# SPI_Bus_Buffer.net
KiCad netlist of a schematic drawn in EAGLE
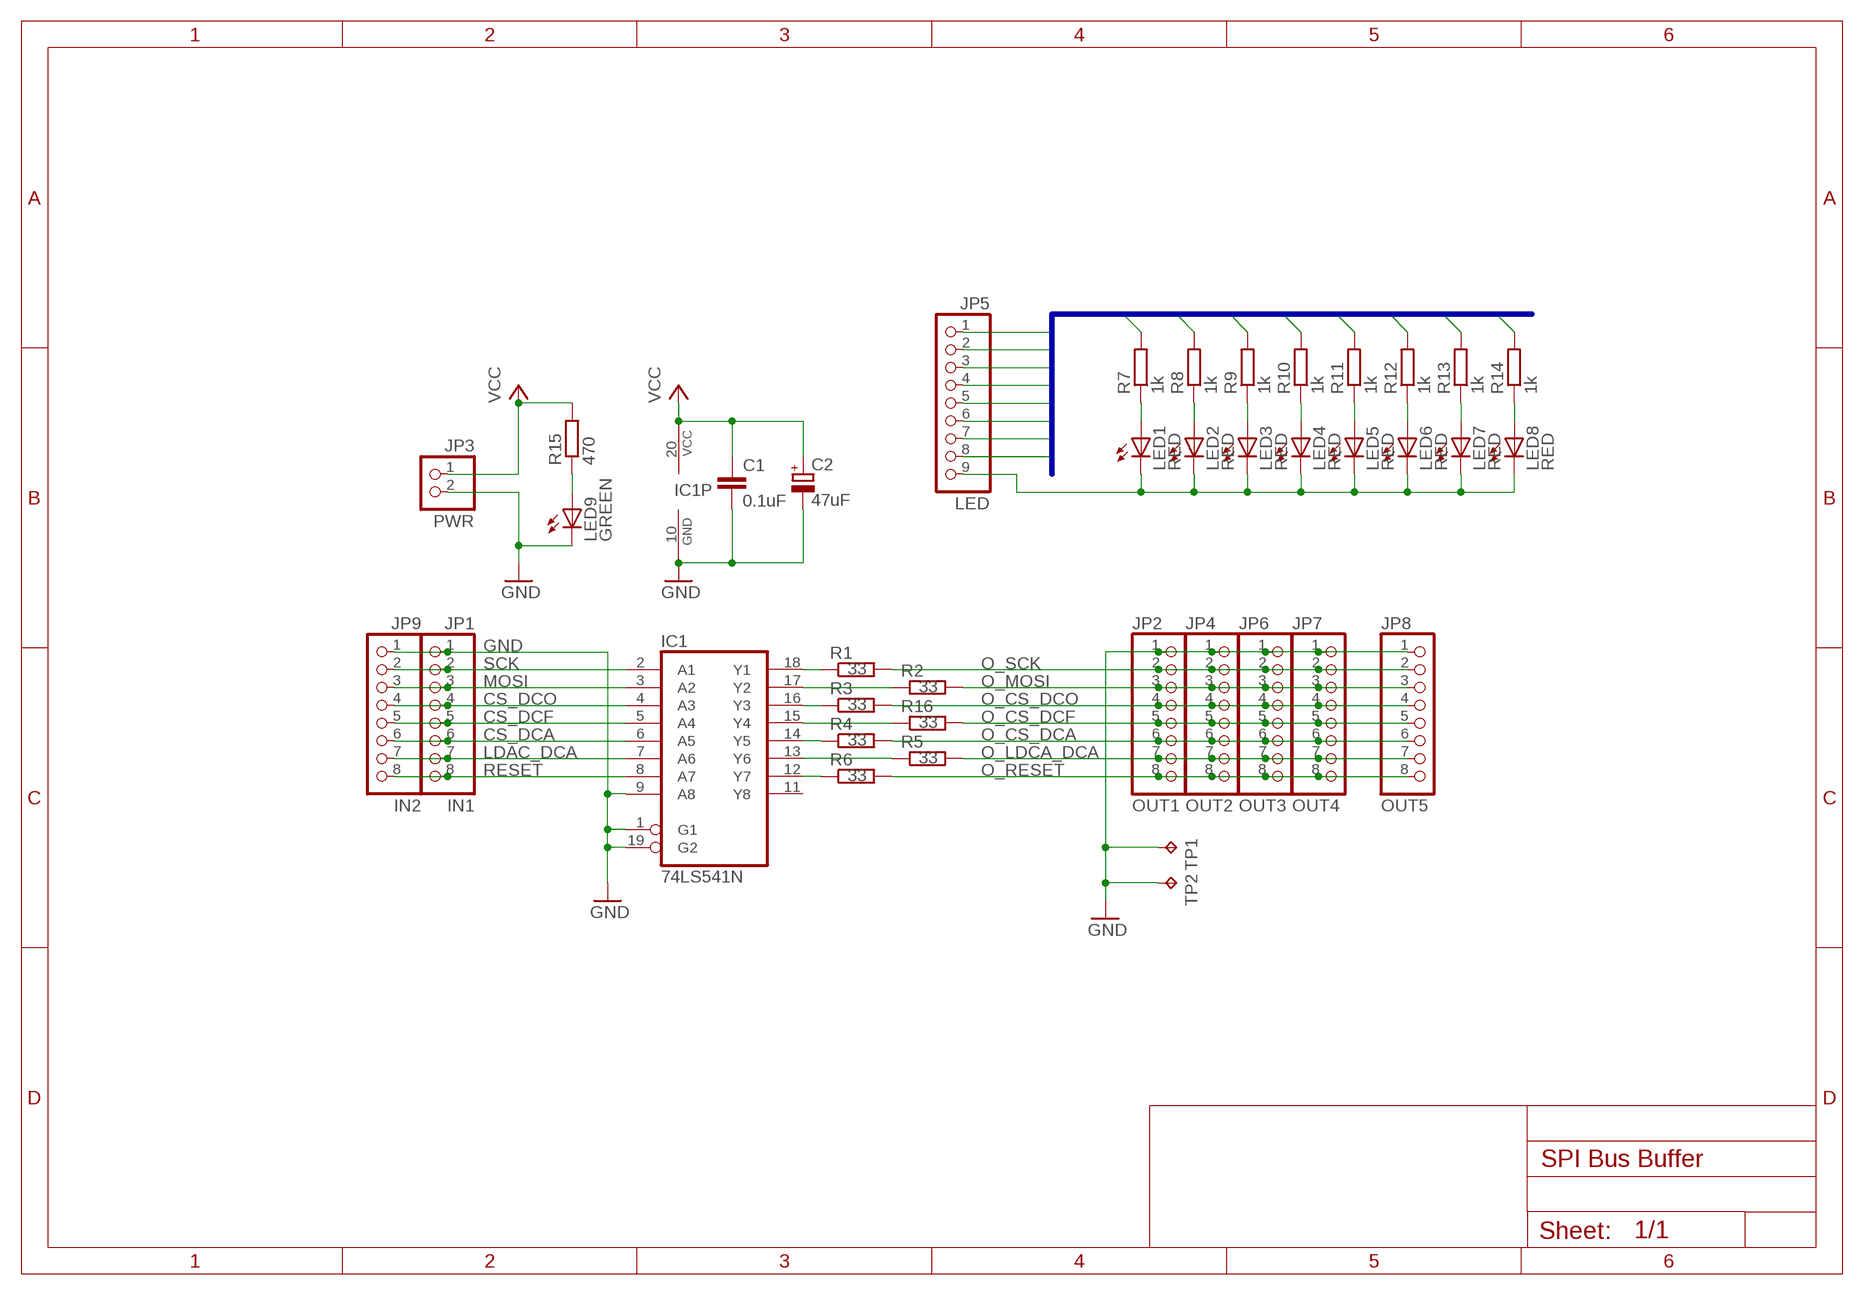
[diagram p0: schematic, sheet 1]

(export (version "E")
  (design (tool "Eeschema 10.0.6"))
  (components
    (comp (ref "C1")
      (value "0.1uF")
      (footprint "eagle-import:C050-024X044")
      (libsource (lib "eagle-import") (part "C-EU050-024X044"))
    )
    (comp (ref "C2")
      (value "47uF")
      (footprint "eagle-import:E2,5-5")
      (libsource (lib "eagle-import") (part "CPOL-EUE2.5-5"))
    )
    (comp (ref "IC1")
      (value "74LS541N")
      (footprint "eagle-import:DIL20")
      (libsource (lib "eagle-import") (part "74541NLS"))
    )
    (comp (ref "JP1")
      (value "IN1")
      (footprint "eagle-import:1X08")
      (libsource (lib "eagle-import") (part "PINHD-1X8"))
    )
    (comp (ref "JP2")
      (value "OUT1")
      (footprint "eagle-import:1X08")
      (libsource (lib "eagle-import") (part "PINHD-1X8"))
    )
    (comp (ref "JP3")
      (value "PWR")
      (footprint "eagle-import:1X02")
      (libsource (lib "eagle-import") (part "PINHD-1X2"))
    )
    (comp (ref "JP4")
      (value "OUT2")
      (footprint "eagle-import:1X08")
      (libsource (lib "eagle-import") (part "PINHD-1X8"))
    )
    (comp (ref "JP5")
      (value "LED")
      (footprint "eagle-import:1X09")
      (libsource (lib "eagle-import") (part "PINHD-1X9"))
    )
    (comp (ref "JP6")
      (value "OUT3")
      (footprint "eagle-import:1X08")
      (libsource (lib "eagle-import") (part "PINHD-1X8"))
    )
    (comp (ref "JP7")
      (value "OUT4")
      (footprint "eagle-import:1X08")
      (libsource (lib "eagle-import") (part "PINHD-1X8"))
    )
    (comp (ref "JP8")
      (value "OUT5")
      (footprint "eagle-import:1X08")
      (libsource (lib "eagle-import") (part "PINHD-1X8"))
    )
    (comp (ref "JP9")
      (value "IN2")
      (footprint "eagle-import:1X08")
      (libsource (lib "eagle-import") (part "PINHD-1X8"))
    )
    (comp (ref "LED1")
      (value "RED")
      (footprint "eagle-import:LED3MM")
      (libsource (lib "eagle-import") (part "LED3MM"))
    )
    (comp (ref "LED2")
      (value "RED")
      (footprint "eagle-import:LED3MM")
      (libsource (lib "eagle-import") (part "LED3MM"))
    )
    (comp (ref "LED3")
      (value "RED")
      (footprint "eagle-import:LED3MM")
      (libsource (lib "eagle-import") (part "LED3MM"))
    )
    (comp (ref "LED4")
      (value "RED")
      (footprint "eagle-import:LED3MM")
      (libsource (lib "eagle-import") (part "LED3MM"))
    )
    (comp (ref "LED5")
      (value "RED")
      (footprint "eagle-import:LED3MM")
      (libsource (lib "eagle-import") (part "LED3MM"))
    )
    (comp (ref "LED6")
      (value "RED")
      (footprint "eagle-import:LED3MM")
      (libsource (lib "eagle-import") (part "LED3MM"))
    )
    (comp (ref "LED7")
      (value "RED")
      (footprint "eagle-import:LED3MM")
      (libsource (lib "eagle-import") (part "LED3MM"))
    )
    (comp (ref "LED8")
      (value "RED")
      (footprint "eagle-import:LED3MM")
      (libsource (lib "eagle-import") (part "LED3MM"))
    )
    (comp (ref "LED9")
      (value "GREEN")
      (footprint "eagle-import:LED3MM")
      (libsource (lib "eagle-import") (part "LED3MM"))
    )
    (comp (ref "R1")
      (value "33")
      (footprint "eagle-import:0207_7")
      (libsource (lib "eagle-import") (part "R-EU_0207/7"))
    )
    (comp (ref "R2")
      (value "33")
      (footprint "eagle-import:0207_7")
      (libsource (lib "eagle-import") (part "R-EU_0207/7"))
    )
    (comp (ref "R3")
      (value "33")
      (footprint "eagle-import:0207_7")
      (libsource (lib "eagle-import") (part "R-EU_0207/7"))
    )
    (comp (ref "R4")
      (value "33")
      (footprint "eagle-import:0207_7")
      (libsource (lib "eagle-import") (part "R-EU_0207/7"))
    )
    (comp (ref "R5")
      (value "33")
      (footprint "eagle-import:0207_7")
      (libsource (lib "eagle-import") (part "R-EU_0207/7"))
    )
    (comp (ref "R6")
      (value "33")
      (footprint "eagle-import:0207_7")
      (libsource (lib "eagle-import") (part "R-EU_0207/7"))
    )
    (comp (ref "R7")
      (value "1k")
      (footprint "eagle-import:0207_7")
      (libsource (lib "eagle-import") (part "R-EU_0207/7"))
    )
    (comp (ref "R8")
      (value "1k")
      (footprint "eagle-import:0207_7")
      (libsource (lib "eagle-import") (part "R-EU_0207/7"))
    )
    (comp (ref "R9")
      (value "1k")
      (footprint "eagle-import:0207_7")
      (libsource (lib "eagle-import") (part "R-EU_0207/7"))
    )
    (comp (ref "R10")
      (value "1k")
      (footprint "eagle-import:0207_7")
      (libsource (lib "eagle-import") (part "R-EU_0207/7"))
    )
    (comp (ref "R11")
      (value "1k")
      (footprint "eagle-import:0207_7")
      (libsource (lib "eagle-import") (part "R-EU_0207/7"))
    )
    (comp (ref "R12")
      (value "1k")
      (footprint "eagle-import:0207_7")
      (libsource (lib "eagle-import") (part "R-EU_0207/7"))
    )
    (comp (ref "R13")
      (value "1k")
      (footprint "eagle-import:0207_7")
      (libsource (lib "eagle-import") (part "R-EU_0207/7"))
    )
    (comp (ref "R14")
      (value "1k")
      (footprint "eagle-import:0207_7")
      (libsource (lib "eagle-import") (part "R-EU_0207/7"))
    )
    (comp (ref "R15")
      (value "470")
      (footprint "eagle-import:0207_7")
      (libsource (lib "eagle-import") (part "R-EU_0207/7"))
    )
    (comp (ref "R16")
      (value "33")
      (footprint "eagle-import:0207_7")
      (libsource (lib "eagle-import") (part "R-EU_0207/7"))
    )
    (comp (ref "TP1")
      (value "TPPAD1-13")
      (footprint "eagle-import:P1-13")
      (libsource (lib "eagle-import") (part "TPPAD1-13"))
    )
    (comp (ref "TP2")
      (value "TPPAD1-13")
      (footprint "eagle-import:P1-13")
      (libsource (lib "eagle-import") (part "TPPAD1-13"))
    )
  )
  (nets
    (net (code "1") (name "/CS_DCA") (class "Default")
      (node (ref "IC1") (pin "6") (pinfunction "A5_6") (pintype "input"))
      (node (ref "JP1") (pin "6") (pinfunction "6_6") (pintype "passive"))
      (node (ref "JP9") (pin "6") (pinfunction "6_6") (pintype "passive"))
    )
    (net (code "2") (name "/CS_DCF") (class "Default")
      (node (ref "IC1") (pin "5") (pinfunction "A4_5") (pintype "input"))
      (node (ref "JP1") (pin "5") (pinfunction "5_5") (pintype "passive"))
      (node (ref "JP9") (pin "5") (pinfunction "5_5") (pintype "passive"))
    )
    (net (code "3") (name "/CS_DCO") (class "Default")
      (node (ref "IC1") (pin "4") (pinfunction "A3_4") (pintype "input"))
      (node (ref "JP1") (pin "4") (pinfunction "4_4") (pintype "passive"))
      (node (ref "JP9") (pin "4") (pinfunction "4_4") (pintype "passive"))
    )
    (net (code "4") (name "/LDAC_DCA") (class "Default")
      (node (ref "IC1") (pin "7") (pinfunction "A6_7") (pintype "input"))
      (node (ref "JP1") (pin "7") (pinfunction "7_7") (pintype "passive"))
      (node (ref "JP9") (pin "7") (pinfunction "7_7") (pintype "passive"))
    )
    (net (code "5") (name "/LEDS1") (class "Default")
      (node (ref "JP5") (pin "1") (pinfunction "1_1") (pintype "passive"))
      (node (ref "R7") (pin "2") (pinfunction "2_2") (pintype "passive"))
    )
    (net (code "6") (name "/LEDS2") (class "Default")
      (node (ref "JP5") (pin "2") (pinfunction "2_2") (pintype "passive"))
      (node (ref "R8") (pin "2") (pinfunction "2_2") (pintype "passive"))
    )
    (net (code "7") (name "/LEDS3") (class "Default")
      (node (ref "JP5") (pin "3") (pinfunction "3_3") (pintype "passive"))
      (node (ref "R9") (pin "2") (pinfunction "2_2") (pintype "passive"))
    )
    (net (code "8") (name "/LEDS4") (class "Default")
      (node (ref "JP5") (pin "4") (pinfunction "4_4") (pintype "passive"))
      (node (ref "R10") (pin "2") (pinfunction "2_2") (pintype "passive"))
    )
    (net (code "9") (name "/LEDS5") (class "Default")
      (node (ref "JP5") (pin "5") (pinfunction "5_5") (pintype "passive"))
      (node (ref "R11") (pin "2") (pinfunction "2_2") (pintype "passive"))
    )
    (net (code "10") (name "/LEDS6") (class "Default")
      (node (ref "JP5") (pin "6") (pinfunction "6_6") (pintype "passive"))
      (node (ref "R12") (pin "2") (pinfunction "2_2") (pintype "passive"))
    )
    (net (code "11") (name "/LEDS7") (class "Default")
      (node (ref "JP5") (pin "7") (pinfunction "7_7") (pintype "passive"))
      (node (ref "R13") (pin "2") (pinfunction "2_2") (pintype "passive"))
    )
    (net (code "12") (name "/LEDS8") (class "Default")
      (node (ref "JP5") (pin "8") (pinfunction "8_8") (pintype "passive"))
      (node (ref "R14") (pin "2") (pinfunction "2_2") (pintype "passive"))
    )
    (net (code "13") (name "/MOSI") (class "Default")
      (node (ref "IC1") (pin "3") (pinfunction "A2_3") (pintype "input"))
      (node (ref "JP1") (pin "3") (pinfunction "3_3") (pintype "passive"))
      (node (ref "JP9") (pin "3") (pinfunction "3_3") (pintype "passive"))
    )
    (net (code "14") (name "/O_CS_DCA") (class "Default")
      (node (ref "JP2") (pin "6") (pinfunction "6_6") (pintype "passive"))
      (node (ref "JP4") (pin "6") (pinfunction "6_6") (pintype "passive"))
      (node (ref "JP6") (pin "6") (pinfunction "6_6") (pintype "passive"))
      (node (ref "JP7") (pin "6") (pinfunction "6_6") (pintype "passive"))
      (node (ref "JP8") (pin "6") (pinfunction "6_6") (pintype "passive"))
      (node (ref "R4") (pin "2") (pinfunction "2_2") (pintype "passive"))
    )
    (net (code "15") (name "/O_CS_DCF") (class "Default")
      (node (ref "JP2") (pin "5") (pinfunction "5_5") (pintype "passive"))
      (node (ref "JP4") (pin "5") (pinfunction "5_5") (pintype "passive"))
      (node (ref "JP6") (pin "5") (pinfunction "5_5") (pintype "passive"))
      (node (ref "JP7") (pin "5") (pinfunction "5_5") (pintype "passive"))
      (node (ref "JP8") (pin "5") (pinfunction "5_5") (pintype "passive"))
      (node (ref "R16") (pin "2") (pinfunction "2_2") (pintype "passive"))
    )
    (net (code "16") (name "/O_CS_DCO") (class "Default")
      (node (ref "JP2") (pin "4") (pinfunction "4_4") (pintype "passive"))
      (node (ref "JP4") (pin "4") (pinfunction "4_4") (pintype "passive"))
      (node (ref "JP6") (pin "4") (pinfunction "4_4") (pintype "passive"))
      (node (ref "JP7") (pin "4") (pinfunction "4_4") (pintype "passive"))
      (node (ref "JP8") (pin "4") (pinfunction "4_4") (pintype "passive"))
      (node (ref "R3") (pin "2") (pinfunction "2_2") (pintype "passive"))
    )
    (net (code "17") (name "/O_LDCA_DCA") (class "Default")
      (node (ref "JP2") (pin "7") (pinfunction "7_7") (pintype "passive"))
      (node (ref "JP4") (pin "7") (pinfunction "7_7") (pintype "passive"))
      (node (ref "JP6") (pin "7") (pinfunction "7_7") (pintype "passive"))
      (node (ref "JP7") (pin "7") (pinfunction "7_7") (pintype "passive"))
      (node (ref "JP8") (pin "7") (pinfunction "7_7") (pintype "passive"))
      (node (ref "R5") (pin "2") (pinfunction "2_2") (pintype "passive"))
    )
    (net (code "18") (name "/O_MOSI") (class "Default")
      (node (ref "JP2") (pin "3") (pinfunction "3_3") (pintype "passive"))
      (node (ref "JP4") (pin "3") (pinfunction "3_3") (pintype "passive"))
      (node (ref "JP6") (pin "3") (pinfunction "3_3") (pintype "passive"))
      (node (ref "JP7") (pin "3") (pinfunction "3_3") (pintype "passive"))
      (node (ref "JP8") (pin "3") (pinfunction "3_3") (pintype "passive"))
      (node (ref "R2") (pin "2") (pinfunction "2_2") (pintype "passive"))
    )
    (net (code "19") (name "/O_RESET") (class "Default")
      (node (ref "JP2") (pin "8") (pinfunction "8_8") (pintype "passive"))
      (node (ref "JP4") (pin "8") (pinfunction "8_8") (pintype "passive"))
      (node (ref "JP6") (pin "8") (pinfunction "8_8") (pintype "passive"))
      (node (ref "JP7") (pin "8") (pinfunction "8_8") (pintype "passive"))
      (node (ref "JP8") (pin "8") (pinfunction "8_8") (pintype "passive"))
      (node (ref "R6") (pin "2") (pinfunction "2_2") (pintype "passive"))
    )
    (net (code "20") (name "/O_SCK") (class "Default")
      (node (ref "JP2") (pin "2") (pinfunction "2_2") (pintype "passive"))
      (node (ref "JP4") (pin "2") (pinfunction "2_2") (pintype "passive"))
      (node (ref "JP6") (pin "2") (pinfunction "2_2") (pintype "passive"))
      (node (ref "JP7") (pin "2") (pinfunction "2_2") (pintype "passive"))
      (node (ref "JP8") (pin "2") (pinfunction "2_2") (pintype "passive"))
      (node (ref "R1") (pin "2") (pinfunction "2_2") (pintype "passive"))
    )
    (net (code "21") (name "/RESET") (class "Default")
      (node (ref "IC1") (pin "8") (pinfunction "A7_8") (pintype "input"))
      (node (ref "JP1") (pin "8") (pinfunction "8_8") (pintype "passive"))
      (node (ref "JP9") (pin "8") (pinfunction "8_8") (pintype "passive"))
    )
    (net (code "22") (name "/SCK") (class "Default")
      (node (ref "IC1") (pin "2") (pinfunction "A1_2") (pintype "input"))
      (node (ref "JP1") (pin "2") (pinfunction "2_2") (pintype "passive"))
      (node (ref "JP9") (pin "2") (pinfunction "2_2") (pintype "passive"))
    )
    (net (code "23") (name "GND") (class "Default")
      (node (ref "C1") (pin "2") (pinfunction "2_2") (pintype "passive"))
      (node (ref "C2") (pin "-") (pinfunction "-_-") (pintype "passive"))
      (node (ref "IC1") (pin "1") (pinfunction "G1_1") (pintype "input"))
      (node (ref "IC1") (pin "10") (pinfunction "GND_10") (pintype "power_in"))
      (node (ref "IC1") (pin "19") (pinfunction "G2_19") (pintype "input"))
      (node (ref "IC1") (pin "9") (pinfunction "A8_9") (pintype "input"))
      (node (ref "JP1") (pin "1") (pinfunction "1_1") (pintype "passive"))
      (node (ref "JP2") (pin "1") (pinfunction "1_1") (pintype "passive"))
      (node (ref "JP3") (pin "2") (pinfunction "2_2") (pintype "passive"))
      (node (ref "JP4") (pin "1") (pinfunction "1_1") (pintype "passive"))
      (node (ref "JP6") (pin "1") (pinfunction "1_1") (pintype "passive"))
      (node (ref "JP7") (pin "1") (pinfunction "1_1") (pintype "passive"))
      (node (ref "JP8") (pin "1") (pinfunction "1_1") (pintype "passive"))
      (node (ref "JP9") (pin "1") (pinfunction "1_1") (pintype "passive"))
      (node (ref "LED9") (pin "K") (pinfunction "C_K") (pintype "passive"))
      (node (ref "TP1") (pin "TP") (pinfunction "TP_TP") (pintype "input"))
      (node (ref "TP2") (pin "TP") (pinfunction "TP_TP") (pintype "input"))
    )
    (net (code "24") (name "Net-(IC1A-Y1)") (class "Default")
      (node (ref "IC1") (pin "18") (pinfunction "Y1_18") (pintype "tri_state"))
      (node (ref "R1") (pin "1") (pinfunction "1_1") (pintype "passive"))
    )
    (net (code "25") (name "Net-(IC1A-Y2)") (class "Default")
      (node (ref "IC1") (pin "17") (pinfunction "Y2_17") (pintype "tri_state"))
      (node (ref "R2") (pin "1") (pinfunction "1_1") (pintype "passive"))
    )
    (net (code "26") (name "Net-(IC1A-Y3)") (class "Default")
      (node (ref "IC1") (pin "16") (pinfunction "Y3_16") (pintype "tri_state"))
      (node (ref "R3") (pin "1") (pinfunction "1_1") (pintype "passive"))
    )
    (net (code "27") (name "Net-(IC1A-Y4)") (class "Default")
      (node (ref "IC1") (pin "15") (pinfunction "Y4_15") (pintype "tri_state"))
      (node (ref "R16") (pin "1") (pinfunction "1_1") (pintype "passive"))
    )
    (net (code "28") (name "Net-(IC1A-Y5)") (class "Default")
      (node (ref "IC1") (pin "14") (pinfunction "Y5_14") (pintype "tri_state"))
      (node (ref "R4") (pin "1") (pinfunction "1_1") (pintype "passive"))
    )
    (net (code "29") (name "Net-(IC1A-Y6)") (class "Default")
      (node (ref "IC1") (pin "13") (pinfunction "Y6_13") (pintype "tri_state"))
      (node (ref "R5") (pin "1") (pinfunction "1_1") (pintype "passive"))
    )
    (net (code "30") (name "Net-(IC1A-Y7)") (class "Default")
      (node (ref "IC1") (pin "12") (pinfunction "Y7_12") (pintype "tri_state"))
      (node (ref "R6") (pin "1") (pinfunction "1_1") (pintype "passive"))
    )
    (net (code "31") (name "Net-(LED1-C)") (class "Default")
      (node (ref "JP5") (pin "9") (pinfunction "9_9") (pintype "passive"))
      (node (ref "LED1") (pin "K") (pinfunction "C_K") (pintype "passive"))
      (node (ref "LED2") (pin "K") (pinfunction "C_K") (pintype "passive"))
      (node (ref "LED3") (pin "K") (pinfunction "C_K") (pintype "passive"))
      (node (ref "LED4") (pin "K") (pinfunction "C_K") (pintype "passive"))
      (node (ref "LED5") (pin "K") (pinfunction "C_K") (pintype "passive"))
      (node (ref "LED6") (pin "K") (pinfunction "C_K") (pintype "passive"))
      (node (ref "LED7") (pin "K") (pinfunction "C_K") (pintype "passive"))
      (node (ref "LED8") (pin "K") (pinfunction "C_K") (pintype "passive"))
    )
    (net (code "32") (name "Net-(LED1-PadA)") (class "Default")
      (node (ref "LED1") (pin "A") (pinfunction "A_A") (pintype "passive"))
      (node (ref "R7") (pin "1") (pinfunction "1_1") (pintype "passive"))
    )
    (net (code "33") (name "Net-(LED2-PadA)") (class "Default")
      (node (ref "LED2") (pin "A") (pinfunction "A_A") (pintype "passive"))
      (node (ref "R8") (pin "1") (pinfunction "1_1") (pintype "passive"))
    )
    (net (code "34") (name "Net-(LED3-PadA)") (class "Default")
      (node (ref "LED3") (pin "A") (pinfunction "A_A") (pintype "passive"))
      (node (ref "R9") (pin "1") (pinfunction "1_1") (pintype "passive"))
    )
    (net (code "35") (name "Net-(LED4-PadA)") (class "Default")
      (node (ref "LED4") (pin "A") (pinfunction "A_A") (pintype "passive"))
      (node (ref "R10") (pin "1") (pinfunction "1_1") (pintype "passive"))
    )
    (net (code "36") (name "Net-(LED5-PadA)") (class "Default")
      (node (ref "LED5") (pin "A") (pinfunction "A_A") (pintype "passive"))
      (node (ref "R11") (pin "1") (pinfunction "1_1") (pintype "passive"))
    )
    (net (code "37") (name "Net-(LED6-PadA)") (class "Default")
      (node (ref "LED6") (pin "A") (pinfunction "A_A") (pintype "passive"))
      (node (ref "R12") (pin "1") (pinfunction "1_1") (pintype "passive"))
    )
    (net (code "38") (name "Net-(LED7-PadA)") (class "Default")
      (node (ref "LED7") (pin "A") (pinfunction "A_A") (pintype "passive"))
      (node (ref "R13") (pin "1") (pinfunction "1_1") (pintype "passive"))
    )
    (net (code "39") (name "Net-(LED8-PadA)") (class "Default")
      (node (ref "LED8") (pin "A") (pinfunction "A_A") (pintype "passive"))
      (node (ref "R14") (pin "1") (pinfunction "1_1") (pintype "passive"))
    )
    (net (code "40") (name "Net-(LED9-PadA)") (class "Default")
      (node (ref "LED9") (pin "A") (pinfunction "A_A") (pintype "passive"))
      (node (ref "R15") (pin "1") (pinfunction "1_1") (pintype "passive"))
    )
    (net (code "41") (name "VCC") (class "Default")
      (node (ref "C1") (pin "1") (pinfunction "1_1") (pintype "passive"))
      (node (ref "C2") (pin "+") (pinfunction "+_+") (pintype "passive"))
      (node (ref "IC1") (pin "20") (pinfunction "VCC_20") (pintype "power_in"))
      (node (ref "JP3") (pin "1") (pinfunction "1_1") (pintype "passive"))
      (node (ref "R15") (pin "2") (pinfunction "2_2") (pintype "passive"))
    )
    (net (code "42") (name "unconnected-(IC1A-Y8-Pad11)") (class "Default")
      (node (ref "IC1") (pin "11") (pinfunction "Y8_11") (pintype "tri_state"))
    )
  )
)
